# LEDs.net
KiCad netlist of a schematic drawn in Altium Designer
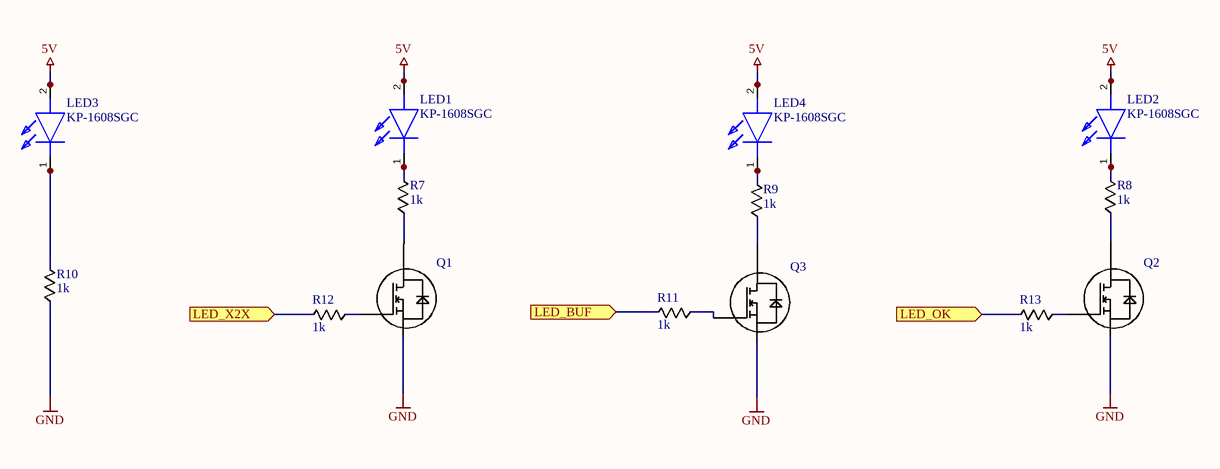
[diagram p0: LEDs.SchDoc]

(export (version "E")
  (design (tool "Eeschema 10.0.6"))
  (components
    (comp (ref "LED1")
      (value "KP-1608SGC")
      (footprint "IGAS Elements:KP-1608SGC")
      (libsource (lib "IGAS Elements") (part "KP-1608SGC"))
    )
    (comp (ref "LED2")
      (value "KP-1608SGC")
      (footprint "IGAS Elements:KP-1608SGC")
      (libsource (lib "IGAS Elements") (part "KP-1608SGC"))
    )
    (comp (ref "LED3")
      (value "KP-1608SGC")
      (footprint "IGAS Elements:KP-1608SGC")
      (libsource (lib "IGAS Elements") (part "KP-1608SGC"))
    )
    (comp (ref "LED4")
      (value "KP-1608SGC")
      (footprint "IGAS Elements:KP-1608SGC")
      (libsource (lib "IGAS Elements") (part "KP-1608SGC"))
    )
    (comp (ref "Q1")
      (value "MOSFET-N")
      (footprint "SOT-23")
      (description "IRLML2502TR")
      (libsource (lib "IGAS Elements") (part "BSS138"))
    )
    (comp (ref "Q2")
      (value "MOSFET-N")
      (footprint "SOT-23")
      (description "IRLML2502TR")
      (libsource (lib "IGAS Elements") (part "BSS138"))
    )
    (comp (ref "Q3")
      (value "MOSFET-N")
      (footprint "SOT-23")
      (description "IRLML2502TR")
      (libsource (lib "IGAS Elements") (part "BSS138"))
    )
    (comp (ref "R7") (value "1k") (footprint "0603 CAP") (libsource (lib "IGAS Elements") (part "0603 RES")))
    (comp (ref "R8") (value "1k") (footprint "0603 CAP") (libsource (lib "IGAS Elements") (part "0603 RES")))
    (comp (ref "R9") (value "1k") (footprint "0603 CAP") (libsource (lib "IGAS Elements") (part "0603 RES")))
    (comp (ref "R10") (value "1k") (footprint "0603 CAP") (libsource (lib "IGAS Elements") (part "0603 RES")))
    (comp (ref "R11") (value "1k") (footprint "0603 CAP") (libsource (lib "IGAS Elements") (part "0603 RES")))
    (comp (ref "R12") (value "1k") (footprint "0603 CAP") (libsource (lib "IGAS Elements") (part "0603 RES")))
    (comp (ref "R13") (value "1k") (footprint "0603 CAP") (libsource (lib "IGAS Elements") (part "0603 RES")))
  )
  (nets
    (net (code "1") (name "/LED_BUF") (class "Default") (node (ref "R11") (pin "2") (pintype "passive")))
    (net (code "2") (name "/LED_OK") (class "Default") (node (ref "R13") (pin "2") (pintype "passive")))
    (net (code "3") (name "/LED_X2X") (class "Default") (node (ref "R12") (pin "2") (pintype "passive")))
    (net (code "4") (name "5V") (class "Default")
      (node (ref "LED1") (pin "2") (pinfunction "A_2") (pintype "passive"))
      (node (ref "LED2") (pin "2") (pinfunction "A_2") (pintype "passive"))
      (node (ref "LED3") (pin "2") (pinfunction "A_2") (pintype "passive"))
      (node (ref "LED4") (pin "2") (pinfunction "A_2") (pintype "passive"))
    )
    (net (code "5") (name "GND") (class "Default")
      (node (ref "Q1") (pin "2") (pinfunction "S_2") (pintype "passive"))
      (node (ref "Q2") (pin "2") (pinfunction "S_2") (pintype "passive"))
      (node (ref "Q3") (pin "2") (pinfunction "S_2") (pintype "passive"))
      (node (ref "R10") (pin "1") (pintype "passive"))
    )
    (net (code "6") (name "Net-(LED1-K)") (class "Default")
      (node (ref "LED1") (pin "1") (pinfunction "K_1") (pintype "passive"))
      (node (ref "R7") (pin "2") (pintype "passive"))
    )
    (net (code "7") (name "Net-(LED2-K)") (class "Default")
      (node (ref "LED2") (pin "1") (pinfunction "K_1") (pintype "passive"))
      (node (ref "R8") (pin "2") (pintype "passive"))
    )
    (net (code "8") (name "Net-(LED3-K)") (class "Default")
      (node (ref "LED3") (pin "1") (pinfunction "K_1") (pintype "passive"))
      (node (ref "R10") (pin "2") (pintype "passive"))
    )
    (net (code "9") (name "Net-(LED4-K)") (class "Default")
      (node (ref "LED4") (pin "1") (pinfunction "K_1") (pintype "passive"))
      (node (ref "R9") (pin "2") (pintype "passive"))
    )
    (net (code "10") (name "Net-(Q1-D)") (class "Default")
      (node (ref "Q1") (pin "3") (pinfunction "D_3") (pintype "passive"))
      (node (ref "R7") (pin "1") (pintype "passive"))
    )
    (net (code "11") (name "Net-(Q1-G)") (class "Default")
      (node (ref "Q1") (pin "1") (pinfunction "G_1") (pintype "passive"))
      (node (ref "R12") (pin "1") (pintype "passive"))
    )
    (net (code "12") (name "Net-(Q2-D)") (class "Default")
      (node (ref "Q2") (pin "3") (pinfunction "D_3") (pintype "passive"))
      (node (ref "R8") (pin "1") (pintype "passive"))
    )
    (net (code "13") (name "Net-(Q2-G)") (class "Default")
      (node (ref "Q2") (pin "1") (pinfunction "G_1") (pintype "passive"))
      (node (ref "R13") (pin "1") (pintype "passive"))
    )
    (net (code "14") (name "Net-(Q3-D)") (class "Default")
      (node (ref "Q3") (pin "3") (pinfunction "D_3") (pintype "passive"))
      (node (ref "R9") (pin "1") (pintype "passive"))
    )
    (net (code "15") (name "Net-(Q3-G)") (class "Default")
      (node (ref "Q3") (pin "1") (pinfunction "G_1") (pintype "passive"))
      (node (ref "R11") (pin "1") (pintype "passive"))
    )
  )
)
